# Fyre-PPG-Module.net
KiCad netlist of a schematic drawn in EAGLE
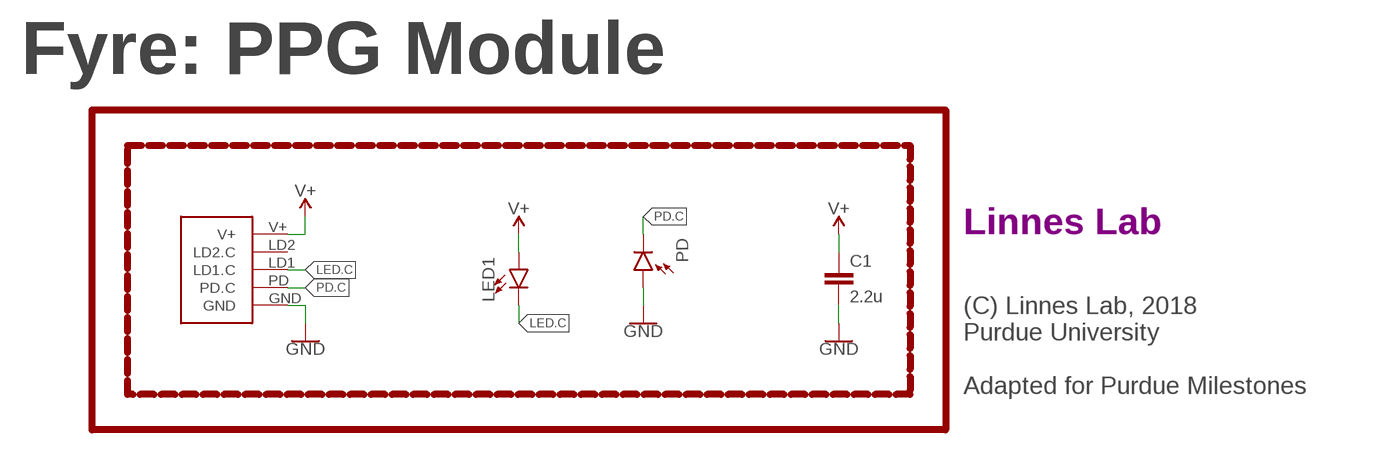
[diagram p0: schematic, sheet 1]

(export (version "E")
  (design (tool "Eeschema 10.0.6"))
  (components
    (comp (ref "C1")
      (value "2.2u")
      (footprint "eagle-import:C0603")
      (libsource (lib "eagle-import") (part "CAPACITOR0603"))
    )
    (comp (ref "J1")
      (value "PPG.MODULE.2")
      (footprint "eagle-import:PPG.MODULE.2")
      (libsource (lib "eagle-import") (part "PPG.MODULE.2"))
    )
    (comp (ref "LED1")
      (value "LED0805")
      (footprint "eagle-import:LED-0805")
      (libsource (lib "eagle-import") (part "LED0805"))
    )
    (comp (ref "PD")
      (value "PHOTODIODE.-SMD.GULLWING")
      (footprint "eagle-import:2-SMD.GULLWING")
      (libsource (lib "eagle-import") (part "PHOTODIODE.-SMD.GULLWING"))
    )
    (comp (ref "U$3")
      (value "LINNES.LAB.LOGO")
      (footprint "eagle-import:LINNES.LAB.LOGO")
      (libsource (lib "eagle-import") (part "LINNES.LAB.LOGO"))
    )
  )
  (nets
    (net (code "1") (name "GND") (class "Default")
      (node (ref "C1") (pin "2") (pinfunction "2_2") (pintype "passive"))
      (node (ref "J1") (pin "GND") (pinfunction "GND_GND") (pintype "bidirectional"))
      (node (ref "PD") (pin "+") (pinfunction "A_+") (pintype "passive"))
    )
    (net (code "2") (name "LED.C") (class "Default")
      (node (ref "J1") (pin "LD1") (pinfunction "LD1.C_LD1") (pintype "bidirectional"))
      (node (ref "LED1") (pin "C") (pinfunction "C_C") (pintype "passive"))
    )
    (net (code "3") (name "PD.C") (class "Default")
      (node (ref "J1") (pin "PD") (pinfunction "PD.C_PD") (pintype "bidirectional"))
      (node (ref "PD") (pin "-") (pinfunction "C_-") (pintype "passive"))
    )
    (net (code "4") (name "V+") (class "Default")
      (node (ref "C1") (pin "1") (pinfunction "1_1") (pintype "passive"))
      (node (ref "J1") (pin "V+") (pinfunction "V+_V+") (pintype "bidirectional"))
      (node (ref "LED1") (pin "A") (pinfunction "A_A") (pintype "passive"))
    )
    (net (code "5") (name "unconnected-(J1-LD2.C-PadLD2)") (class "Default")
      (node (ref "J1") (pin "LD2") (pinfunction "LD2.C_LD2") (pintype "bidirectional"))
    )
  )
)
